# WatchdogTimer.net
KiCad netlist of a schematic drawn in EAGLE
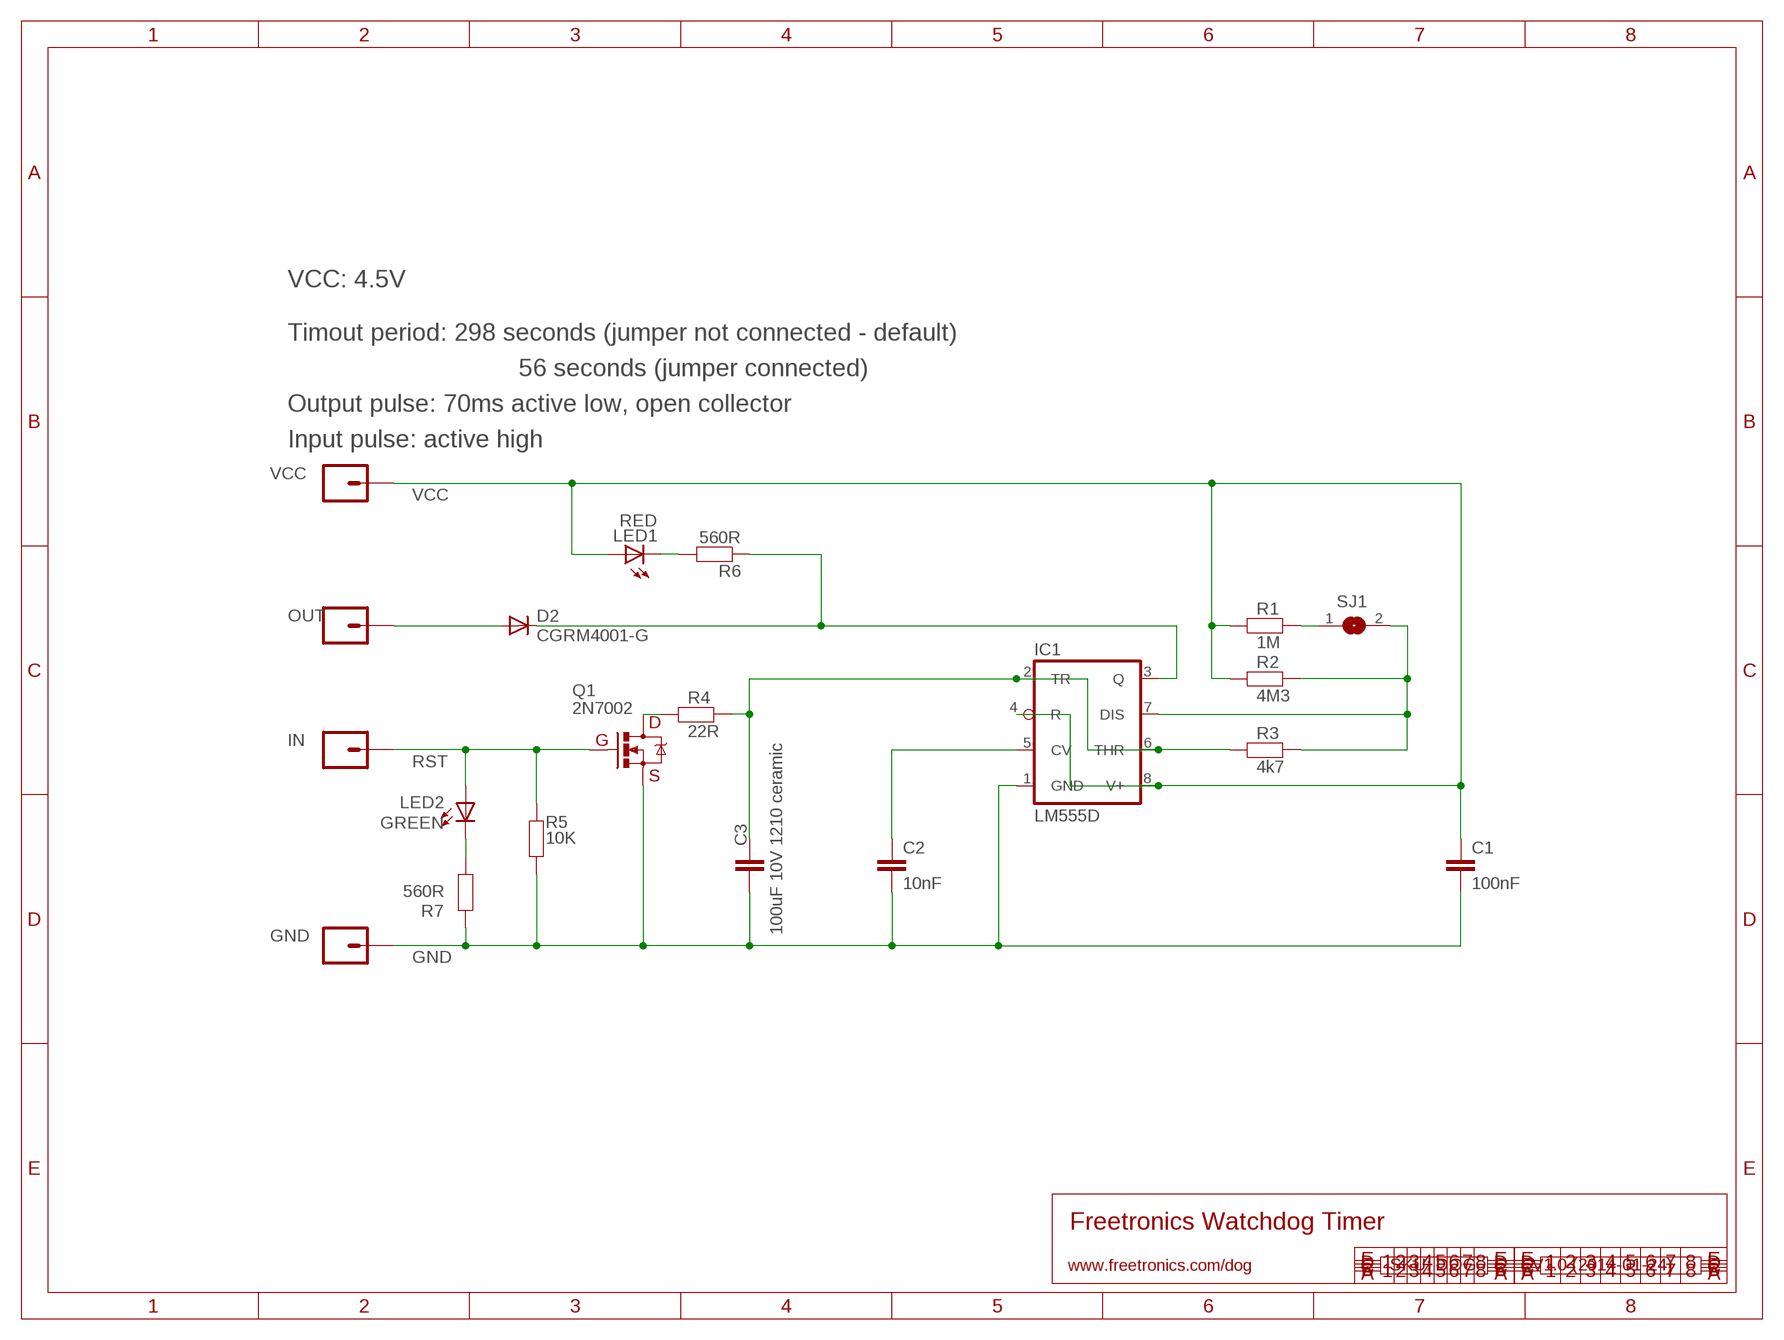
[diagram p0: schematic, sheet 1]

(export (version "E")
  (design (tool "Eeschema 10.0.6"))
  (components
    (comp (ref "C1")
      (value "100nF")
      (footprint "eagle-import:0603")
      (libsource (lib "eagle-import") (part "CAP0603"))
    )
    (comp (ref "C2")
      (value "10nF")
      (footprint "eagle-import:0603")
      (libsource (lib "eagle-import") (part "CAP0603"))
    )
    (comp (ref "C3")
      (value "100uF 10V 1210 ceramic")
      (footprint "eagle-import:C1210")
      (libsource (lib "eagle-import") (part "C-EUC1210"))
    )
    (comp (ref "D2")
      (value "CGRM4001-G")
      (footprint "eagle-import:SOD-123_MINI-SMA")
      (libsource (lib "eagle-import") (part "CGRM400-G1"))
    )
    (comp (ref "GND")
      (value "M01PTH")
      (footprint "eagle-import:1X01")
      (libsource (lib "eagle-import") (part "M01PTH"))
    )
    (comp (ref "IC1")
      (value "LM555D")
      (footprint "eagle-import:SO08")
      (libsource (lib "eagle-import") (part "555DLM"))
    )
    (comp (ref "IN")
      (value "M01PTH")
      (footprint "eagle-import:1X01")
      (libsource (lib "eagle-import") (part "M01PTH"))
    )
    (comp (ref "LED1")
      (value "RED")
      (footprint "eagle-import:LED-0603")
      (libsource (lib "eagle-import") (part "LED0603"))
    )
    (comp (ref "LED2")
      (value "GREEN")
      (footprint "eagle-import:LED-0603")
      (libsource (lib "eagle-import") (part "LED0603"))
    )
    (comp (ref "OUT")
      (value "M01PTH")
      (footprint "eagle-import:1X01")
      (libsource (lib "eagle-import") (part "M01PTH"))
    )
    (comp (ref "Q1")
      (value "2N7002")
      (footprint "eagle-import:SOT23-3")
      (libsource (lib "eagle-import") (part "MOSFET-NCHANNELSMD"))
    )
    (comp (ref "R1")
      (value "1M")
      (footprint "eagle-import:0603")
      (libsource (lib "eagle-import") (part "RESISTOR0603"))
    )
    (comp (ref "R2")
      (value "4M3")
      (footprint "eagle-import:0603")
      (libsource (lib "eagle-import") (part "RESISTOR0603"))
    )
    (comp (ref "R3")
      (value "4k7")
      (footprint "eagle-import:0603")
      (libsource (lib "eagle-import") (part "RESISTOR0603"))
    )
    (comp (ref "R4")
      (value "22R")
      (footprint "eagle-import:0603")
      (libsource (lib "eagle-import") (part "RESISTOR0603"))
    )
    (comp (ref "R5")
      (value "10K")
      (footprint "eagle-import:0603")
      (libsource (lib "eagle-import") (part "RESISTOR0603"))
    )
    (comp (ref "R6")
      (value "560R")
      (footprint "eagle-import:0603")
      (libsource (lib "eagle-import") (part "RESISTOR0603"))
    )
    (comp (ref "R7")
      (value "560R")
      (footprint "eagle-import:0603")
      (libsource (lib "eagle-import") (part "RESISTOR0603"))
    )
    (comp (ref "SJ1") (value "SJ") (footprint "eagle-import:SJ") (libsource (lib "eagle-import") (part "SJ")))
    (comp (ref "VCC")
      (value "M01PTH")
      (footprint "eagle-import:1X01")
      (libsource (lib "eagle-import") (part "M01PTH"))
    )
  )
  (nets
    (net (code "1") (name "/GND") (class "Default")
      (node (ref "C1") (pin "2") (pinfunction "2_2") (pintype "passive"))
      (node (ref "C2") (pin "2") (pinfunction "2_2") (pintype "passive"))
      (node (ref "C3") (pin "2") (pinfunction "2_2") (pintype "passive"))
      (node (ref "GND") (pin "1") (pinfunction "1_1") (pintype "passive"))
      (node (ref "IC1") (pin "1") (pinfunction "GND_1") (pintype "power_in"))
      (node (ref "Q1") (pin "2") (pinfunction "S_2") (pintype "passive"))
      (node (ref "R5") (pin "1") (pinfunction "1_1") (pintype "passive"))
      (node (ref "R7") (pin "2") (pinfunction "2_2") (pintype "passive"))
    )
    (net (code "2") (name "/RST") (class "Default")
      (node (ref "IN") (pin "1") (pinfunction "1_1") (pintype "passive"))
      (node (ref "LED2") (pin "A") (pinfunction "A_A") (pintype "passive"))
      (node (ref "Q1") (pin "1") (pinfunction "G_1") (pintype "passive"))
      (node (ref "R5") (pin "2") (pinfunction "2_2") (pintype "passive"))
    )
    (net (code "3") (name "/VCC") (class "Default")
      (node (ref "C1") (pin "1") (pinfunction "1_1") (pintype "passive"))
      (node (ref "IC1") (pin "4") (pinfunction "R_4") (pintype "input"))
      (node (ref "IC1") (pin "8") (pinfunction "V+_8") (pintype "power_in"))
      (node (ref "LED1") (pin "A") (pinfunction "A_A") (pintype "passive"))
      (node (ref "R1") (pin "1") (pinfunction "1_1") (pintype "passive"))
      (node (ref "R2") (pin "1") (pinfunction "1_1") (pintype "passive"))
      (node (ref "VCC") (pin "1") (pinfunction "1_1") (pintype "passive"))
    )
    (net (code "4") (name "Net-(D2-PadA)") (class "Default")
      (node (ref "D2") (pin "A") (pinfunction "A_A") (pintype "passive"))
      (node (ref "OUT") (pin "1") (pinfunction "1_1") (pintype "passive"))
    )
    (net (code "5") (name "Net-(IC1-CV)") (class "Default")
      (node (ref "C2") (pin "1") (pinfunction "1_1") (pintype "passive"))
      (node (ref "IC1") (pin "5") (pinfunction "CV_5") (pintype "input"))
    )
    (net (code "6") (name "Net-(IC1-DIS)") (class "Default")
      (node (ref "IC1") (pin "7") (pinfunction "DIS_7") (pintype "input"))
      (node (ref "R2") (pin "2") (pinfunction "2_2") (pintype "passive"))
      (node (ref "R3") (pin "2") (pinfunction "2_2") (pintype "passive"))
      (node (ref "SJ1") (pin "2") (pinfunction "2_2") (pintype "passive"))
    )
    (net (code "7") (name "Net-(IC1-Q)") (class "Default")
      (node (ref "D2") (pin "C") (pinfunction "C_C") (pintype "passive"))
      (node (ref "IC1") (pin "3") (pinfunction "Q_3") (pintype "output"))
      (node (ref "R6") (pin "1") (pinfunction "1_1") (pintype "passive"))
    )
    (net (code "8") (name "Net-(IC1-THR)") (class "Default")
      (node (ref "C3") (pin "1") (pinfunction "1_1") (pintype "passive"))
      (node (ref "IC1") (pin "2") (pinfunction "TR_2") (pintype "input"))
      (node (ref "IC1") (pin "6") (pinfunction "THR_6") (pintype "input"))
      (node (ref "R3") (pin "1") (pinfunction "1_1") (pintype "passive"))
      (node (ref "R4") (pin "2") (pinfunction "2_2") (pintype "passive"))
    )
    (net (code "9") (name "Net-(LED1-PadC)") (class "Default")
      (node (ref "LED1") (pin "C") (pinfunction "C_C") (pintype "passive"))
      (node (ref "R6") (pin "2") (pinfunction "2_2") (pintype "passive"))
    )
    (net (code "10") (name "Net-(LED2-PadC)") (class "Default")
      (node (ref "LED2") (pin "C") (pinfunction "C_C") (pintype "passive"))
      (node (ref "R7") (pin "1") (pinfunction "1_1") (pintype "passive"))
    )
    (net (code "11") (name "Net-(Q1-D)") (class "Default")
      (node (ref "Q1") (pin "3") (pinfunction "D_3") (pintype "passive"))
      (node (ref "R4") (pin "1") (pinfunction "1_1") (pintype "passive"))
    )
    (net (code "12") (name "Net-(R1-Pad2)") (class "Default")
      (node (ref "R1") (pin "2") (pinfunction "2_2") (pintype "passive"))
      (node (ref "SJ1") (pin "1") (pinfunction "1_1") (pintype "passive"))
    )
  )
)
